# D_Input.net
KiCad netlist of a schematic drawn in Altium Designer
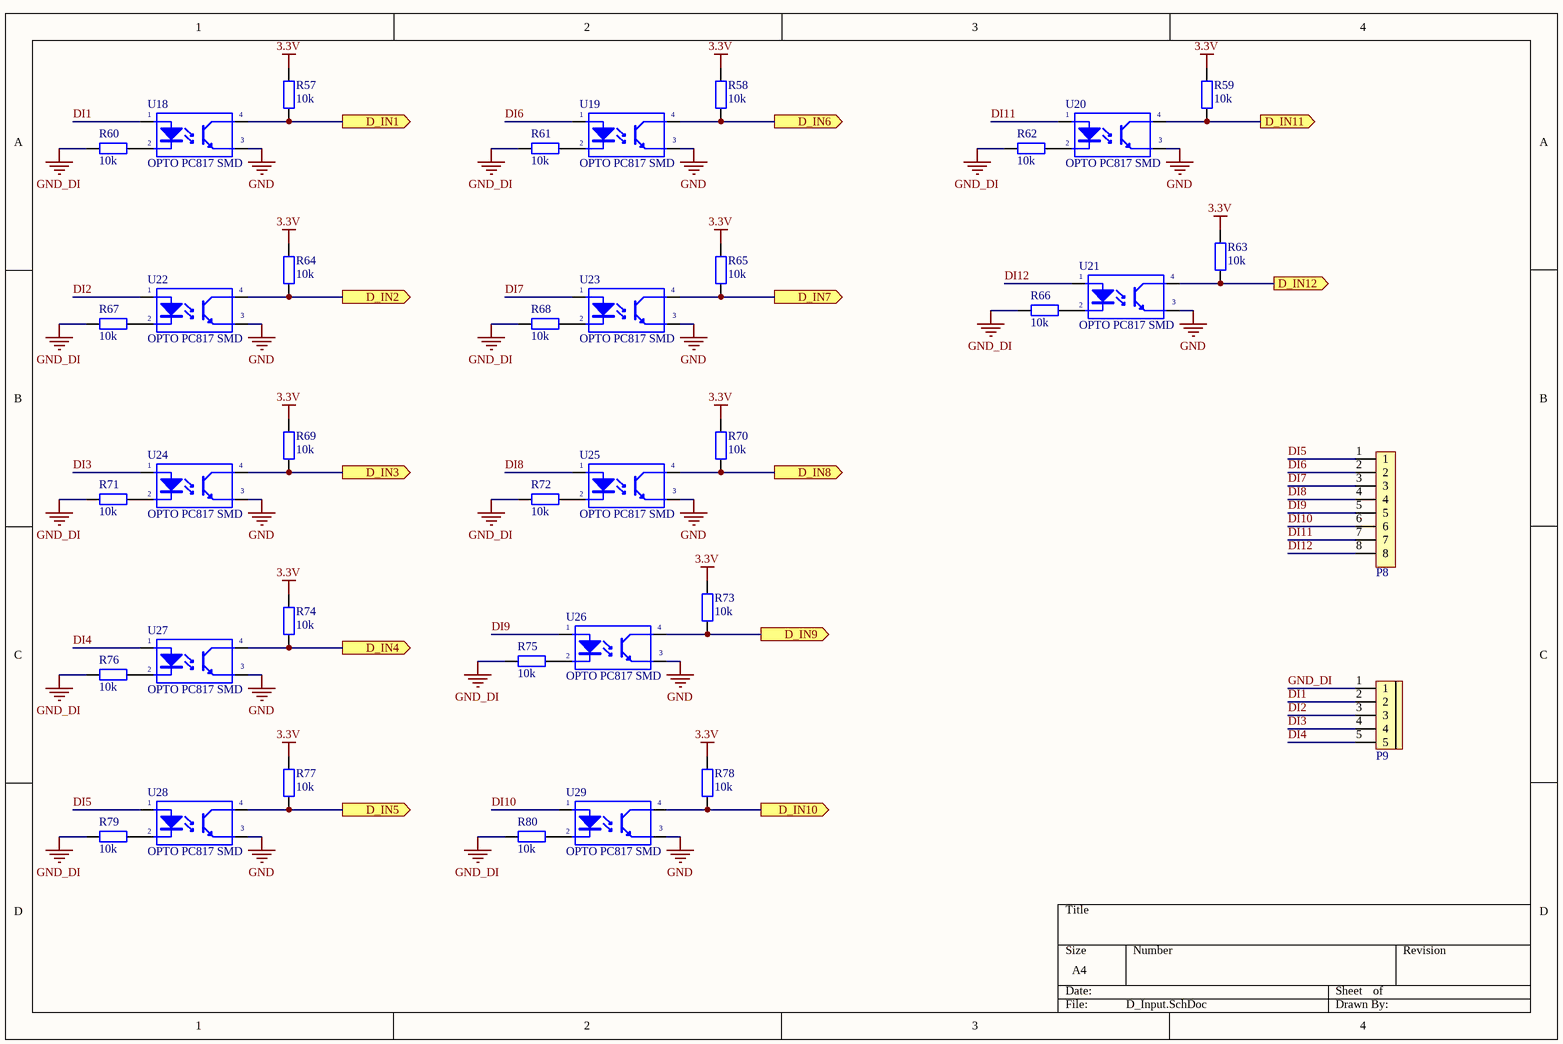
[diagram p0: D_Input.SchDoc]

(export (version "E")
  (design (tool "Eeschema 10.0.6"))
  (components
    (comp (ref "P8")
      (value "CON 8 EDG5.08")
      (footprint "CON 8 8EDG5.08")
      (description "Cắm")
      (libsource (lib "Altium_Lib_by_KhueNguyenCreator") (part "CON 8 EDG5.08"))
    )
    (comp (ref "P9")
      (value "CON 5 EDG5.08")
      (footprint "CON 5 5EDG5.08")
      (description "Cắm")
      (libsource (lib "Altium_Lib_by_KhueNguyenCreator") (part "CON 5 EDG5.08"))
    )
    (comp (ref "R57")
      (value "10k")
      (footprint "tro smd 0603")
      (description "Dán")
      (libsource (lib "Altium_Lib_by_KhueNguyenCreator") (part "Tro 0603 5% 10k"))
    )
    (comp (ref "R58")
      (value "10k")
      (footprint "tro smd 0603")
      (description "Dán")
      (libsource (lib "Altium_Lib_by_KhueNguyenCreator") (part "Tro 0603 5% 10k"))
    )
    (comp (ref "R59")
      (value "10k")
      (footprint "tro smd 0603")
      (description "Dán")
      (libsource (lib "Altium_Lib_by_KhueNguyenCreator") (part "Tro 0603 5% 10k"))
    )
    (comp (ref "R60")
      (value "10k")
      (footprint "tro smd 0603")
      (description "Dán")
      (libsource (lib "Altium_Lib_by_KhueNguyenCreator") (part "Tro 0603 5% 10k"))
    )
    (comp (ref "R61")
      (value "10k")
      (footprint "tro smd 0603")
      (description "Dán")
      (libsource (lib "Altium_Lib_by_KhueNguyenCreator") (part "Tro 0603 5% 10k"))
    )
    (comp (ref "R62")
      (value "10k")
      (footprint "tro smd 0603")
      (description "Dán")
      (libsource (lib "Altium_Lib_by_KhueNguyenCreator") (part "Tro 0603 5% 10k"))
    )
    (comp (ref "R63")
      (value "10k")
      (footprint "tro smd 0603")
      (description "Dán")
      (libsource (lib "Altium_Lib_by_KhueNguyenCreator") (part "Tro 0603 5% 10k"))
    )
    (comp (ref "R64")
      (value "10k")
      (footprint "tro smd 0603")
      (description "Dán")
      (libsource (lib "Altium_Lib_by_KhueNguyenCreator") (part "Tro 0603 5% 10k"))
    )
    (comp (ref "R65")
      (value "10k")
      (footprint "tro smd 0603")
      (description "Dán")
      (libsource (lib "Altium_Lib_by_KhueNguyenCreator") (part "Tro 0603 5% 10k"))
    )
    (comp (ref "R66")
      (value "10k")
      (footprint "tro smd 0603")
      (description "Dán")
      (libsource (lib "Altium_Lib_by_KhueNguyenCreator") (part "Tro 0603 5% 10k"))
    )
    (comp (ref "R67")
      (value "10k")
      (footprint "tro smd 0603")
      (description "Dán")
      (libsource (lib "Altium_Lib_by_KhueNguyenCreator") (part "Tro 0603 5% 10k"))
    )
    (comp (ref "R68")
      (value "10k")
      (footprint "tro smd 0603")
      (description "Dán")
      (libsource (lib "Altium_Lib_by_KhueNguyenCreator") (part "Tro 0603 5% 10k"))
    )
    (comp (ref "R69")
      (value "10k")
      (footprint "tro smd 0603")
      (description "Dán")
      (libsource (lib "Altium_Lib_by_KhueNguyenCreator") (part "Tro 0603 5% 10k"))
    )
    (comp (ref "R70")
      (value "10k")
      (footprint "tro smd 0603")
      (description "Dán")
      (libsource (lib "Altium_Lib_by_KhueNguyenCreator") (part "Tro 0603 5% 10k"))
    )
    (comp (ref "R71")
      (value "10k")
      (footprint "tro smd 0603")
      (description "Dán")
      (libsource (lib "Altium_Lib_by_KhueNguyenCreator") (part "Tro 0603 5% 10k"))
    )
    (comp (ref "R72")
      (value "10k")
      (footprint "tro smd 0603")
      (description "Dán")
      (libsource (lib "Altium_Lib_by_KhueNguyenCreator") (part "Tro 0603 5% 10k"))
    )
    (comp (ref "R73")
      (value "10k")
      (footprint "tro smd 0603")
      (description "Dán")
      (libsource (lib "Altium_Lib_by_KhueNguyenCreator") (part "Tro 0603 5% 10k"))
    )
    (comp (ref "R74")
      (value "10k")
      (footprint "tro smd 0603")
      (description "Dán")
      (libsource (lib "Altium_Lib_by_KhueNguyenCreator") (part "Tro 0603 5% 10k"))
    )
    (comp (ref "R75")
      (value "10k")
      (footprint "tro smd 0603")
      (description "Dán")
      (libsource (lib "Altium_Lib_by_KhueNguyenCreator") (part "Tro 0603 5% 10k"))
    )
    (comp (ref "R76")
      (value "10k")
      (footprint "tro smd 0603")
      (description "Dán")
      (libsource (lib "Altium_Lib_by_KhueNguyenCreator") (part "Tro 0603 5% 10k"))
    )
    (comp (ref "R77")
      (value "10k")
      (footprint "tro smd 0603")
      (description "Dán")
      (libsource (lib "Altium_Lib_by_KhueNguyenCreator") (part "Tro 0603 5% 10k"))
    )
    (comp (ref "R78")
      (value "10k")
      (footprint "tro smd 0603")
      (description "Dán")
      (libsource (lib "Altium_Lib_by_KhueNguyenCreator") (part "Tro 0603 5% 10k"))
    )
    (comp (ref "R79")
      (value "10k")
      (footprint "tro smd 0603")
      (description "Dán")
      (libsource (lib "Altium_Lib_by_KhueNguyenCreator") (part "Tro 0603 5% 10k"))
    )
    (comp (ref "R80")
      (value "10k")
      (footprint "tro smd 0603")
      (description "Dán")
      (libsource (lib "Altium_Lib_by_KhueNguyenCreator") (part "Tro 0603 5% 10k"))
    )
    (comp (ref "U18")
      (value "OPTO PC817 SMD")
      (footprint "SOP4")
      (description "Single Opto")
      (libsource (lib "Altium_Lib_by_KhueNguyenCreator") (part "OPTO PC817 SMD"))
    )
    (comp (ref "U19")
      (value "OPTO PC817 SMD")
      (footprint "SOP4")
      (description "Single Opto")
      (libsource (lib "Altium_Lib_by_KhueNguyenCreator") (part "OPTO PC817 SMD"))
    )
    (comp (ref "U20")
      (value "OPTO PC817 SMD")
      (footprint "SOP4")
      (description "Single Opto")
      (libsource (lib "Altium_Lib_by_KhueNguyenCreator") (part "OPTO PC817 SMD"))
    )
    (comp (ref "U21")
      (value "OPTO PC817 SMD")
      (footprint "SOP4")
      (description "Single Opto")
      (libsource (lib "Altium_Lib_by_KhueNguyenCreator") (part "OPTO PC817 SMD"))
    )
    (comp (ref "U22")
      (value "OPTO PC817 SMD")
      (footprint "SOP4")
      (description "Single Opto")
      (libsource (lib "Altium_Lib_by_KhueNguyenCreator") (part "OPTO PC817 SMD"))
    )
    (comp (ref "U23")
      (value "OPTO PC817 SMD")
      (footprint "SOP4")
      (description "Single Opto")
      (libsource (lib "Altium_Lib_by_KhueNguyenCreator") (part "OPTO PC817 SMD"))
    )
    (comp (ref "U24")
      (value "OPTO PC817 SMD")
      (footprint "SOP4")
      (description "Single Opto")
      (libsource (lib "Altium_Lib_by_KhueNguyenCreator") (part "OPTO PC817 SMD"))
    )
    (comp (ref "U25")
      (value "OPTO PC817 SMD")
      (footprint "SOP4")
      (description "Single Opto")
      (libsource (lib "Altium_Lib_by_KhueNguyenCreator") (part "OPTO PC817 SMD"))
    )
    (comp (ref "U26")
      (value "OPTO PC817 SMD")
      (footprint "SOP4")
      (description "Single Opto")
      (libsource (lib "Altium_Lib_by_KhueNguyenCreator") (part "OPTO PC817 SMD"))
    )
    (comp (ref "U27")
      (value "OPTO PC817 SMD")
      (footprint "SOP4")
      (description "Single Opto")
      (libsource (lib "Altium_Lib_by_KhueNguyenCreator") (part "OPTO PC817 SMD"))
    )
    (comp (ref "U28")
      (value "OPTO PC817 SMD")
      (footprint "SOP4")
      (description "Single Opto")
      (libsource (lib "Altium_Lib_by_KhueNguyenCreator") (part "OPTO PC817 SMD"))
    )
    (comp (ref "U29")
      (value "OPTO PC817 SMD")
      (footprint "SOP4")
      (description "Single Opto")
      (libsource (lib "Altium_Lib_by_KhueNguyenCreator") (part "OPTO PC817 SMD"))
    )
  )
  (nets
    (net (code "1") (name "/DI1") (class "Default")
      (node (ref "P9") (pin "2") (pinfunction "2_2") (pintype "passive"))
      (node (ref "U18") (pin "1") (pinfunction "A_1") (pintype "passive"))
    )
    (net (code "2") (name "/DI2") (class "Default")
      (node (ref "P9") (pin "3") (pinfunction "3_3") (pintype "passive"))
      (node (ref "U22") (pin "1") (pinfunction "A_1") (pintype "passive"))
    )
    (net (code "3") (name "/DI3") (class "Default")
      (node (ref "P9") (pin "4") (pinfunction "4_4") (pintype "passive"))
      (node (ref "U24") (pin "1") (pinfunction "A_1") (pintype "passive"))
    )
    (net (code "4") (name "/DI4") (class "Default")
      (node (ref "P9") (pin "5") (pinfunction "5_5") (pintype "passive"))
      (node (ref "U27") (pin "1") (pinfunction "A_1") (pintype "passive"))
    )
    (net (code "5") (name "/DI5") (class "Default")
      (node (ref "P8") (pin "1") (pinfunction "1_1") (pintype "passive"))
      (node (ref "U28") (pin "1") (pinfunction "A_1") (pintype "passive"))
    )
    (net (code "6") (name "/DI6") (class "Default")
      (node (ref "P8") (pin "2") (pinfunction "2_2") (pintype "passive"))
      (node (ref "U19") (pin "1") (pinfunction "A_1") (pintype "passive"))
    )
    (net (code "7") (name "/DI7") (class "Default")
      (node (ref "P8") (pin "3") (pinfunction "3_3") (pintype "passive"))
      (node (ref "U23") (pin "1") (pinfunction "A_1") (pintype "passive"))
    )
    (net (code "8") (name "/DI8") (class "Default")
      (node (ref "P8") (pin "4") (pinfunction "4_4") (pintype "passive"))
      (node (ref "U25") (pin "1") (pinfunction "A_1") (pintype "passive"))
    )
    (net (code "9") (name "/DI9") (class "Default")
      (node (ref "P8") (pin "5") (pinfunction "5_5") (pintype "passive"))
      (node (ref "U26") (pin "1") (pinfunction "A_1") (pintype "passive"))
    )
    (net (code "10") (name "/DI10") (class "Default")
      (node (ref "P8") (pin "6") (pinfunction "6_6") (pintype "passive"))
      (node (ref "U29") (pin "1") (pinfunction "A_1") (pintype "passive"))
    )
    (net (code "11") (name "/DI11") (class "Default")
      (node (ref "P8") (pin "7") (pinfunction "7_7") (pintype "passive"))
      (node (ref "U20") (pin "1") (pinfunction "A_1") (pintype "passive"))
    )
    (net (code "12") (name "/DI12") (class "Default")
      (node (ref "P8") (pin "8") (pinfunction "8_8") (pintype "passive"))
      (node (ref "U21") (pin "1") (pinfunction "A_1") (pintype "passive"))
    )
    (net (code "13") (name "/D_IN1") (class "Default")
      (node (ref "R57") (pin "1") (pinfunction "1_1") (pintype "passive"))
      (node (ref "U18") (pin "4") (pinfunction "C_4") (pintype "passive"))
    )
    (net (code "14") (name "/D_IN2") (class "Default")
      (node (ref "R64") (pin "1") (pinfunction "1_1") (pintype "passive"))
      (node (ref "U22") (pin "4") (pinfunction "C_4") (pintype "passive"))
    )
    (net (code "15") (name "/D_IN3") (class "Default")
      (node (ref "R69") (pin "1") (pinfunction "1_1") (pintype "passive"))
      (node (ref "U24") (pin "4") (pinfunction "C_4") (pintype "passive"))
    )
    (net (code "16") (name "/D_IN4") (class "Default")
      (node (ref "R74") (pin "1") (pinfunction "1_1") (pintype "passive"))
      (node (ref "U27") (pin "4") (pinfunction "C_4") (pintype "passive"))
    )
    (net (code "17") (name "/D_IN5") (class "Default")
      (node (ref "R77") (pin "1") (pinfunction "1_1") (pintype "passive"))
      (node (ref "U28") (pin "4") (pinfunction "C_4") (pintype "passive"))
    )
    (net (code "18") (name "/D_IN6") (class "Default")
      (node (ref "R58") (pin "1") (pinfunction "1_1") (pintype "passive"))
      (node (ref "U19") (pin "4") (pinfunction "C_4") (pintype "passive"))
    )
    (net (code "19") (name "/D_IN7") (class "Default")
      (node (ref "R65") (pin "1") (pinfunction "1_1") (pintype "passive"))
      (node (ref "U23") (pin "4") (pinfunction "C_4") (pintype "passive"))
    )
    (net (code "20") (name "/D_IN8") (class "Default")
      (node (ref "R70") (pin "1") (pinfunction "1_1") (pintype "passive"))
      (node (ref "U25") (pin "4") (pinfunction "C_4") (pintype "passive"))
    )
    (net (code "21") (name "/D_IN9") (class "Default")
      (node (ref "R73") (pin "1") (pinfunction "1_1") (pintype "passive"))
      (node (ref "U26") (pin "4") (pinfunction "C_4") (pintype "passive"))
    )
    (net (code "22") (name "/D_IN10") (class "Default")
      (node (ref "R78") (pin "1") (pinfunction "1_1") (pintype "passive"))
      (node (ref "U29") (pin "4") (pinfunction "C_4") (pintype "passive"))
    )
    (net (code "23") (name "/D_IN11") (class "Default")
      (node (ref "R59") (pin "1") (pinfunction "1_1") (pintype "passive"))
      (node (ref "U20") (pin "4") (pinfunction "C_4") (pintype "passive"))
    )
    (net (code "24") (name "/D_IN12") (class "Default")
      (node (ref "R63") (pin "1") (pinfunction "1_1") (pintype "passive"))
      (node (ref "U21") (pin "4") (pinfunction "C_4") (pintype "passive"))
    )
    (net (code "25") (name "3.3V") (class "Default")
      (node (ref "R57") (pin "2") (pinfunction "2_2") (pintype "passive"))
      (node (ref "R58") (pin "2") (pinfunction "2_2") (pintype "passive"))
      (node (ref "R59") (pin "2") (pinfunction "2_2") (pintype "passive"))
      (node (ref "R63") (pin "2") (pinfunction "2_2") (pintype "passive"))
      (node (ref "R64") (pin "2") (pinfunction "2_2") (pintype "passive"))
      (node (ref "R65") (pin "2") (pinfunction "2_2") (pintype "passive"))
      (node (ref "R69") (pin "2") (pinfunction "2_2") (pintype "passive"))
      (node (ref "R70") (pin "2") (pinfunction "2_2") (pintype "passive"))
      (node (ref "R73") (pin "2") (pinfunction "2_2") (pintype "passive"))
      (node (ref "R74") (pin "2") (pinfunction "2_2") (pintype "passive"))
      (node (ref "R77") (pin "2") (pinfunction "2_2") (pintype "passive"))
      (node (ref "R78") (pin "2") (pinfunction "2_2") (pintype "passive"))
    )
    (net (code "26") (name "GND") (class "Default")
      (node (ref "U18") (pin "3") (pinfunction "E_3") (pintype "passive"))
      (node (ref "U19") (pin "3") (pinfunction "E_3") (pintype "passive"))
      (node (ref "U20") (pin "3") (pinfunction "E_3") (pintype "passive"))
      (node (ref "U21") (pin "3") (pinfunction "E_3") (pintype "passive"))
      (node (ref "U22") (pin "3") (pinfunction "E_3") (pintype "passive"))
      (node (ref "U23") (pin "3") (pinfunction "E_3") (pintype "passive"))
      (node (ref "U24") (pin "3") (pinfunction "E_3") (pintype "passive"))
      (node (ref "U25") (pin "3") (pinfunction "E_3") (pintype "passive"))
      (node (ref "U26") (pin "3") (pinfunction "E_3") (pintype "passive"))
      (node (ref "U27") (pin "3") (pinfunction "E_3") (pintype "passive"))
      (node (ref "U28") (pin "3") (pinfunction "E_3") (pintype "passive"))
      (node (ref "U29") (pin "3") (pinfunction "E_3") (pintype "passive"))
    )
    (net (code "27") (name "GND_DI") (class "Default")
      (node (ref "P9") (pin "1") (pinfunction "1_1") (pintype "passive"))
      (node (ref "R60") (pin "2") (pinfunction "2_2") (pintype "passive"))
      (node (ref "R61") (pin "2") (pinfunction "2_2") (pintype "passive"))
      (node (ref "R62") (pin "2") (pinfunction "2_2") (pintype "passive"))
      (node (ref "R66") (pin "2") (pinfunction "2_2") (pintype "passive"))
      (node (ref "R67") (pin "2") (pinfunction "2_2") (pintype "passive"))
      (node (ref "R68") (pin "2") (pinfunction "2_2") (pintype "passive"))
      (node (ref "R71") (pin "2") (pinfunction "2_2") (pintype "passive"))
      (node (ref "R72") (pin "2") (pinfunction "2_2") (pintype "passive"))
      (node (ref "R75") (pin "2") (pinfunction "2_2") (pintype "passive"))
      (node (ref "R76") (pin "2") (pinfunction "2_2") (pintype "passive"))
      (node (ref "R79") (pin "2") (pinfunction "2_2") (pintype "passive"))
      (node (ref "R80") (pin "2") (pinfunction "2_2") (pintype "passive"))
    )
    (net (code "28") (name "Net-(U18-K)") (class "Default")
      (node (ref "R60") (pin "1") (pinfunction "1_1") (pintype "passive"))
      (node (ref "U18") (pin "2") (pinfunction "K_2") (pintype "passive"))
    )
    (net (code "29") (name "Net-(U19-K)") (class "Default")
      (node (ref "R61") (pin "1") (pinfunction "1_1") (pintype "passive"))
      (node (ref "U19") (pin "2") (pinfunction "K_2") (pintype "passive"))
    )
    (net (code "30") (name "Net-(U20-K)") (class "Default")
      (node (ref "R62") (pin "1") (pinfunction "1_1") (pintype "passive"))
      (node (ref "U20") (pin "2") (pinfunction "K_2") (pintype "passive"))
    )
    (net (code "31") (name "Net-(U21-K)") (class "Default")
      (node (ref "R66") (pin "1") (pinfunction "1_1") (pintype "passive"))
      (node (ref "U21") (pin "2") (pinfunction "K_2") (pintype "passive"))
    )
    (net (code "32") (name "Net-(U22-K)") (class "Default")
      (node (ref "R67") (pin "1") (pinfunction "1_1") (pintype "passive"))
      (node (ref "U22") (pin "2") (pinfunction "K_2") (pintype "passive"))
    )
    (net (code "33") (name "Net-(U23-K)") (class "Default")
      (node (ref "R68") (pin "1") (pinfunction "1_1") (pintype "passive"))
      (node (ref "U23") (pin "2") (pinfunction "K_2") (pintype "passive"))
    )
    (net (code "34") (name "Net-(U24-K)") (class "Default")
      (node (ref "R71") (pin "1") (pinfunction "1_1") (pintype "passive"))
      (node (ref "U24") (pin "2") (pinfunction "K_2") (pintype "passive"))
    )
    (net (code "35") (name "Net-(U25-K)") (class "Default")
      (node (ref "R72") (pin "1") (pinfunction "1_1") (pintype "passive"))
      (node (ref "U25") (pin "2") (pinfunction "K_2") (pintype "passive"))
    )
    (net (code "36") (name "Net-(U26-K)") (class "Default")
      (node (ref "R75") (pin "1") (pinfunction "1_1") (pintype "passive"))
      (node (ref "U26") (pin "2") (pinfunction "K_2") (pintype "passive"))
    )
    (net (code "37") (name "Net-(U27-K)") (class "Default")
      (node (ref "R76") (pin "1") (pinfunction "1_1") (pintype "passive"))
      (node (ref "U27") (pin "2") (pinfunction "K_2") (pintype "passive"))
    )
    (net (code "38") (name "Net-(U28-K)") (class "Default")
      (node (ref "R79") (pin "1") (pinfunction "1_1") (pintype "passive"))
      (node (ref "U28") (pin "2") (pinfunction "K_2") (pintype "passive"))
    )
    (net (code "39") (name "Net-(U29-K)") (class "Default")
      (node (ref "R80") (pin "1") (pinfunction "1_1") (pintype "passive"))
      (node (ref "U29") (pin "2") (pinfunction "K_2") (pintype "passive"))
    )
  )
)
